# Main.net
KiCad netlist of a schematic drawn in Altium Designer
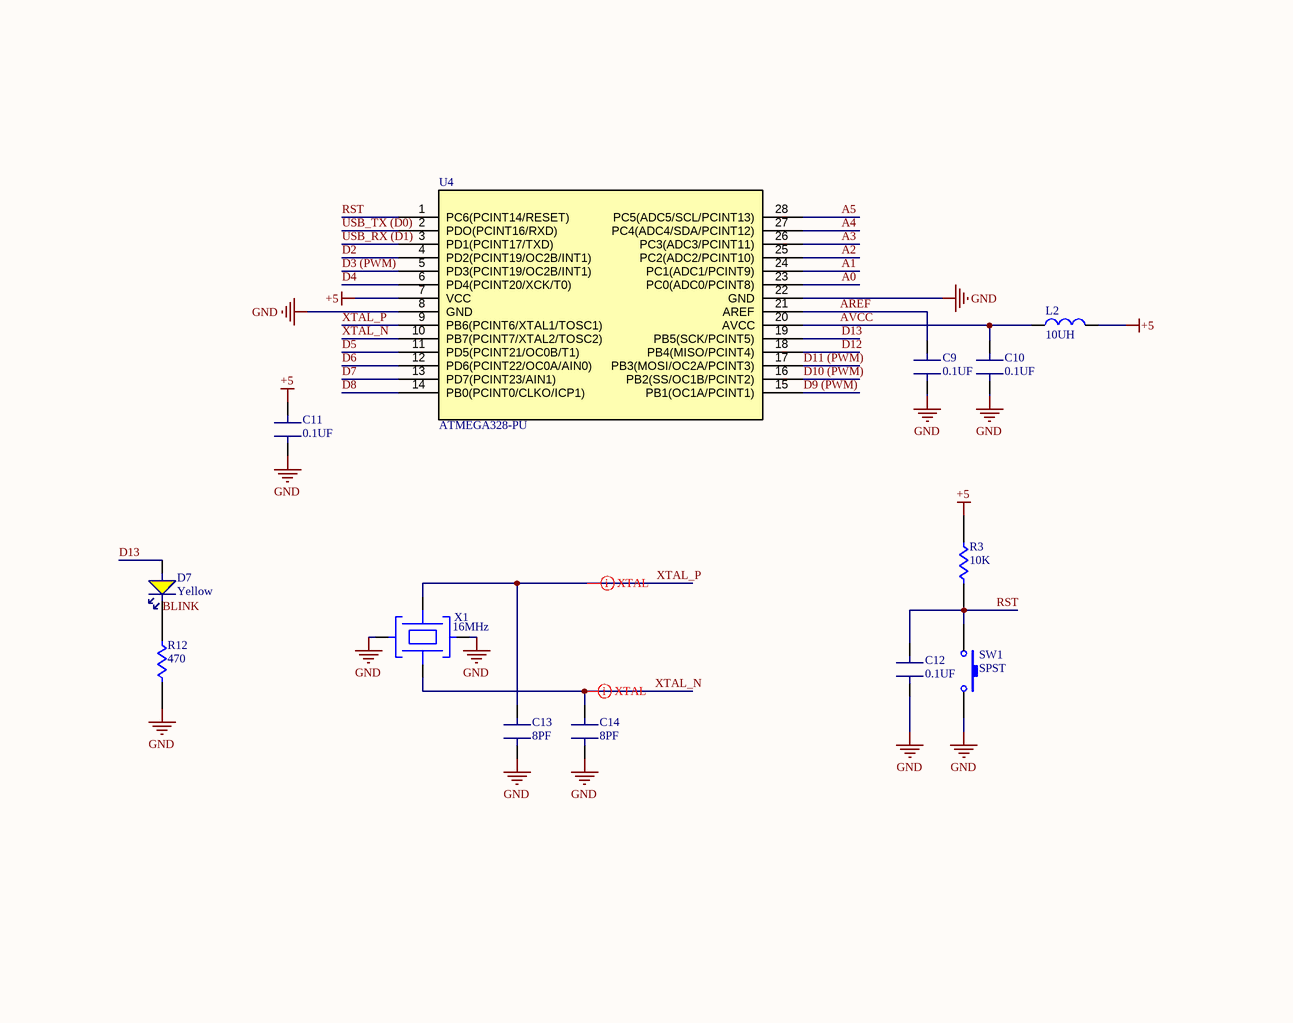
[diagram p0: Main.SchDoc]

(export (version "E")
  (design (tool "Eeschema 10.0.6"))
  (components
    (comp (ref "C9")
      (value "0.1UF")
      (footprint "CAPC1608X90N")
      (description "CAP CER 0.1UF 50V 10% X7R 0603")
      (libsource (lib "MESchLib") (part "CC0603KRX7R9BB104"))
    )
    (comp (ref "C10")
      (value "0.1UF")
      (footprint "CAPC1608X90N")
      (description "CAP CER 0.1UF 50V 10% X7R 0603")
      (libsource (lib "MESchLib") (part "CC0603KRX7R9BB104"))
    )
    (comp (ref "C11")
      (value "0.1UF")
      (footprint "CAPC1608X90N")
      (description "CAP CER 0.1UF 50V 10% X7R 0603")
      (libsource (lib "MESchLib") (part "CC0603KRX7R9BB104"))
    )
    (comp (ref "C12")
      (value "0.1UF")
      (footprint "CAP: 0603")
      (description "CAP CER 0.1UF 50V 10% X7R 0603")
      (libsource (lib "HZSchLib") (part "CC0603KRX7R9BB104"))
    )
    (comp (ref "C13")
      (value "8PF")
      (footprint "CAP: 0603")
      (description "CAP CER 8PF 50V C0G/NPO 0603")
      (libsource (lib "MESchLib") (part "CC0603DRNPO9BN8R0"))
    )
    (comp (ref "C14")
      (value "8PF")
      (footprint "CAP: 0603")
      (description "CAP CER 8PF 50V C0G/NPO 0603")
      (libsource (lib "MESchLib") (part "CC0603DRNPO9BN8R0"))
    )
    (comp (ref "D7")
      (value "Yellow")
      (footprint "LED: 0805Y")
      (description "LED YELLOW CLEAR 0805 SMD")
      (libsource (lib "MESchLib") (part "150080YS75000"))
    )
    (comp (ref "L2")
      (value "10UH")
      (footprint "IND: 1210")
      (description "FIXED IND 10UH 250MA 240MOHM SMD")
      (libsource (lib "MESchLib") (part "NLFV32T-100K-EF"))
    )
    (comp (ref "R3")
      (value "10K")
      (footprint "RESC1608X55N")
      (description "RES SMD 10K OHM 1% 1/10W 0603")
      (libsource (lib "MESchLib") (part "RC0603FR-0710KL"))
    )
    (comp (ref "R12")
      (value "470")
      (footprint "RESC1608X55N")
      (description "RES 470 OHM 5% 1/10W 0603")
      (libsource (lib "MESchLib") (part "541-4055-6-ND"))
    )
    (comp (ref "SW1")
      (value "SPST")
      (footprint "MJTP1106STRB")
      (description "SWITCH TACTILE SPST-NO 0.05A 12V")
      (libsource (lib "HZSchLib") (part "MJTP1106STR"))
    )
    (comp (ref "U4")
      (value "ATMEGA328-PU")
      (footprint "dip_28")
      (description "AVR AVR® ATmega Microcontroller IC 8-Bit 20MHz 32KB (16K x 16) FLASH 28-PDIP")
      (libsource (lib "MESchLib") (part "ATMEGA328-PU"))
    )
    (comp (ref "X1")
      (value "16MHz")
      (footprint "4-SMD, No Lead")
      (description "CRYSTAL 16.0000MHZ 10PF SMD")
      (libsource (lib "MESchLib") (part "ECS-160-10-36-CKM-TR3"))
    )
  )
  (nets
    (net (code "1") (name "+5") (class "Default")
      (node (ref "C11") (pin "1") (pinfunction "A_1") (pintype "passive"))
      (node (ref "L2") (pin "2") (pinfunction "A_2") (pintype "passive"))
      (node (ref "R3") (pin "2") (pinfunction "2_2") (pintype "passive"))
      (node (ref "U4") (pin "7") (pinfunction "VCC_7") (pintype "passive"))
    )
    (net (code "2") (name "/A0") (class "Default")
      (node (ref "U4") (pin "23") (pinfunction "PC0(ADC0/PCINT8)_23") (pintype "passive"))
    )
    (net (code "3") (name "/A1") (class "Default")
      (node (ref "U4") (pin "24") (pinfunction "PC1(ADC1/PCINT9)_24") (pintype "passive"))
    )
    (net (code "4") (name "/A2") (class "Default")
      (node (ref "U4") (pin "25") (pinfunction "PC2(ADC2/PCINT10)_25") (pintype "passive"))
    )
    (net (code "5") (name "/A3") (class "Default")
      (node (ref "U4") (pin "26") (pinfunction "PC3(ADC3/PCINT11)_26") (pintype "passive"))
    )
    (net (code "6") (name "/A4") (class "Default")
      (node (ref "U4") (pin "27") (pinfunction "PC4(ADC4/SDA/PCINT12)_27") (pintype "passive"))
    )
    (net (code "7") (name "/A5") (class "Default")
      (node (ref "U4") (pin "28") (pinfunction "PC5(ADC5/SCL/PCINT13)_28") (pintype "passive"))
    )
    (net (code "8") (name "/AREF") (class "Default")
      (node (ref "C9") (pin "1") (pinfunction "A_1") (pintype "passive"))
      (node (ref "U4") (pin "21") (pinfunction "AREF_21") (pintype "passive"))
    )
    (net (code "9") (name "/AVCC") (class "Default")
      (node (ref "C10") (pin "1") (pinfunction "A_1") (pintype "passive"))
      (node (ref "L2") (pin "1") (pinfunction "A_1") (pintype "passive"))
      (node (ref "U4") (pin "20") (pinfunction "AVCC_20") (pintype "passive"))
    )
    (net (code "10") (name "/BLINK") (class "Default")
      (node (ref "D7") (pin "1") (pinfunction "C_1") (pintype "passive"))
      (node (ref "R12") (pin "2") (pinfunction "2_2") (pintype "passive"))
    )
    (net (code "11") (name "/D2") (class "Default")
      (node (ref "U4") (pin "4") (pinfunction "PD2(PCINT19/OC2B/INT1)_4") (pintype "passive"))
    )
    (net (code "12") (name "/D3 (PWM)") (class "Default")
      (node (ref "U4") (pin "5") (pinfunction "PD3(PCINT19/OC2B/INT1)_5") (pintype "passive"))
    )
    (net (code "13") (name "/D4") (class "Default")
      (node (ref "U4") (pin "6") (pinfunction "PD4(PCINT20/XCK/T0)_6") (pintype "passive"))
    )
    (net (code "14") (name "/D5") (class "Default")
      (node (ref "U4") (pin "11") (pinfunction "PD5(PCINT21/OC0B/T1)_11") (pintype "passive"))
    )
    (net (code "15") (name "/D6") (class "Default")
      (node (ref "U4") (pin "12") (pinfunction "PD6(PCINT22/OC0A/AIN0)_12") (pintype "passive"))
    )
    (net (code "16") (name "/D7") (class "Default")
      (node (ref "U4") (pin "13") (pinfunction "PD7(PCINT23/AIN1)_13") (pintype "passive"))
    )
    (net (code "17") (name "/D8") (class "Default")
      (node (ref "U4") (pin "14") (pinfunction "PB0(PCINT0/CLKO/ICP1)_14") (pintype "passive"))
    )
    (net (code "18") (name "/D9 (PWM)") (class "Default")
      (node (ref "U4") (pin "15") (pinfunction "PB1(OC1A/PCINT1)_15") (pintype "passive"))
    )
    (net (code "19") (name "/D10 (PWM)") (class "Default")
      (node (ref "U4") (pin "16") (pinfunction "PB2(SS/OC1B/PCINT2)_16") (pintype "passive"))
    )
    (net (code "20") (name "/D11 (PWM)") (class "Default")
      (node (ref "U4") (pin "17") (pinfunction "PB3(MOSI/OC2A/PCINT3)_17") (pintype "passive"))
    )
    (net (code "21") (name "/D12") (class "Default")
      (node (ref "U4") (pin "18") (pinfunction "PB4(MISO/PCINT4)_18") (pintype "passive"))
    )
    (net (code "22") (name "/D13") (class "Default")
      (node (ref "D7") (pin "2") (pinfunction "A_2") (pintype "passive"))
      (node (ref "U4") (pin "19") (pinfunction "PB5(SCK/PCINT5)_19") (pintype "passive"))
    )
    (net (code "23") (name "/RST") (class "Default")
      (node (ref "C12") (pin "2") (pinfunction "B_2") (pintype "passive"))
      (node (ref "R3") (pin "1") (pinfunction "1_1") (pintype "passive"))
      (node (ref "SW1") (pin "2") (pinfunction "2_2") (pintype "passive"))
      (node (ref "U4") (pin "1") (pinfunction "PC6(PCINT14/RESET)_1") (pintype "passive"))
    )
    (net (code "24") (name "/USB_RX (D1)") (class "Default")
      (node (ref "U4") (pin "3") (pinfunction "PD1(PCINT17/TXD)_3") (pintype "passive"))
    )
    (net (code "25") (name "/USB_TX (D0)") (class "Default")
      (node (ref "U4") (pin "2") (pinfunction "PDO(PCINT16/RXD)_2") (pintype "passive"))
    )
    (net (code "26") (name "/XTAL_N") (class "Default")
      (node (ref "C14") (pin "2") (pinfunction "B_2") (pintype "passive"))
      (node (ref "U4") (pin "10") (pinfunction "PB7(PCINT7/XTAL2/TOSC2)_10") (pintype "passive"))
      (node (ref "X1") (pin "3") (pinfunction "3_3") (pintype "passive"))
    )
    (net (code "27") (name "/XTAL_P") (class "Default")
      (node (ref "C13") (pin "2") (pinfunction "B_2") (pintype "passive"))
      (node (ref "U4") (pin "9") (pinfunction "PB6(PCINT6/XTAL1/TOSC1)_9") (pintype "passive"))
      (node (ref "X1") (pin "1") (pinfunction "1_1") (pintype "passive"))
    )
    (net (code "28") (name "GND") (class "Default")
      (node (ref "C10") (pin "2") (pinfunction "B_2") (pintype "passive"))
      (node (ref "C11") (pin "2") (pinfunction "B_2") (pintype "passive"))
      (node (ref "C12") (pin "1") (pinfunction "A_1") (pintype "passive"))
      (node (ref "C13") (pin "1") (pinfunction "A_1") (pintype "passive"))
      (node (ref "C14") (pin "1") (pinfunction "A_1") (pintype "passive"))
      (node (ref "C9") (pin "2") (pinfunction "B_2") (pintype "passive"))
      (node (ref "R12") (pin "1") (pinfunction "1_1") (pintype "passive"))
      (node (ref "SW1") (pin "1") (pinfunction "1_1") (pintype "passive"))
      (node (ref "U4") (pin "22") (pinfunction "GND_22") (pintype "passive"))
      (node (ref "U4") (pin "8") (pinfunction "GND_8") (pintype "passive"))
      (node (ref "X1") (pin "2") (pinfunction "2_2") (pintype "passive"))
      (node (ref "X1") (pin "4") (pinfunction "4_4") (pintype "passive"))
    )
  )
)
